# nRF52832_MCU.net
KiCad netlist of a schematic drawn in Altium Designer
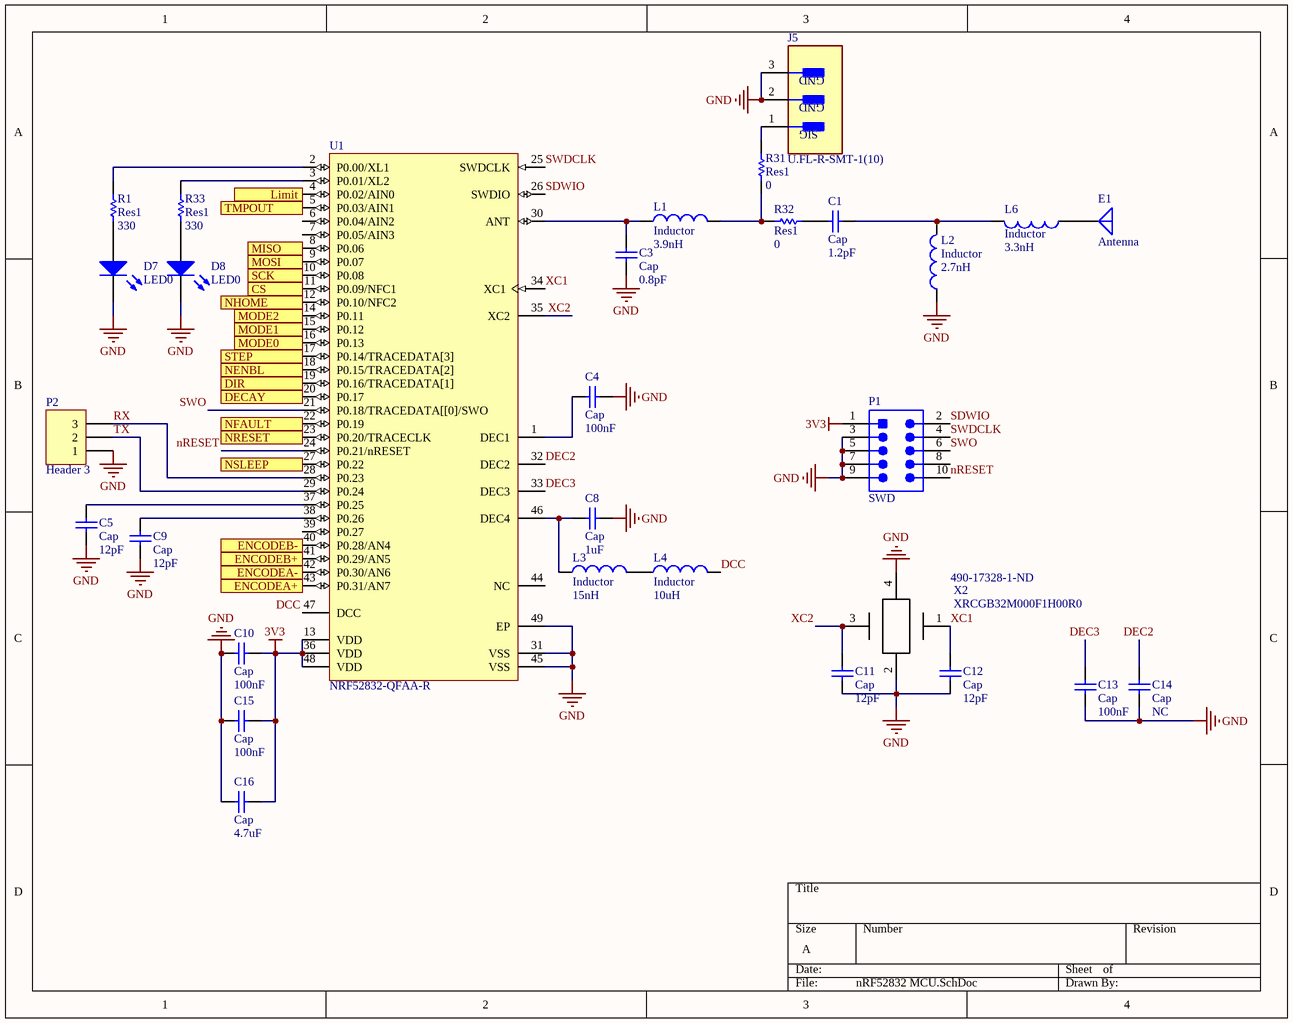
[diagram p0: nRF52832 MCU.SchDoc]

(export (version "E")
  (design (tool "Eeschema 10.0.6"))
  (components
    (comp (ref "C1")
      (value "Cap")
      (footprint "0402-A")
      (description "Capacitor")
      (fields (field (name "ALTIUM_VALUE") "1.2pF") (field (name "PUBLISHER") "Altium Limited"))
      (libsource (lib "Miscellaneous Devices") (part "Cap"))
    )
    (comp (ref "C3")
      (value "Cap")
      (footprint "0402-A")
      (description "Capacitor")
      (fields (field (name "ALTIUM_VALUE") "0.8pF") (field (name "PUBLISHER") "Altium Limited"))
      (libsource (lib "Miscellaneous Devices") (part "Cap"))
    )
    (comp (ref "C4")
      (value "Cap")
      (footprint "1608[0603]")
      (description "Capacitor")
      (fields (field (name "ALTIUM_VALUE") "100nF") (field (name "PUBLISHER") "Altium Limited"))
      (libsource (lib "Miscellaneous Devices") (part "Cap"))
    )
    (comp (ref "C5")
      (value "Cap")
      (footprint "0402-A")
      (description "Capacitor")
      (fields (field (name "ALTIUM_VALUE") "12pF") (field (name "PUBLISHER") "Altium Limited"))
      (libsource (lib "Miscellaneous Devices") (part "Cap"))
    )
    (comp (ref "C8")
      (value "Cap")
      (footprint "1608[0603]")
      (description "Capacitor")
      (fields (field (name "ALTIUM_VALUE") "1uF") (field (name "PUBLISHER") "Altium Limited"))
      (libsource (lib "Miscellaneous Devices") (part "Cap"))
    )
    (comp (ref "C9")
      (value "Cap")
      (footprint "0402-A")
      (description "Capacitor")
      (fields (field (name "ALTIUM_VALUE") "12pF") (field (name "PUBLISHER") "Altium Limited"))
      (libsource (lib "Miscellaneous Devices") (part "Cap"))
    )
    (comp (ref "C10")
      (value "Cap")
      (footprint "1608[0603]")
      (description "Capacitor")
      (fields (field (name "ALTIUM_VALUE") "100nF") (field (name "PUBLISHER") "Altium Limited"))
      (libsource (lib "Miscellaneous Devices") (part "Cap"))
    )
    (comp (ref "C11")
      (value "Cap")
      (footprint "0402-A")
      (description "Capacitor")
      (fields (field (name "ALTIUM_VALUE") "12pF") (field (name "PUBLISHER") "Altium Limited"))
      (libsource (lib "Miscellaneous Devices") (part "Cap"))
    )
    (comp (ref "C12")
      (value "Cap")
      (footprint "0402-A")
      (description "Capacitor")
      (fields (field (name "ALTIUM_VALUE") "12pF") (field (name "PUBLISHER") "Altium Limited"))
      (libsource (lib "Miscellaneous Devices") (part "Cap"))
    )
    (comp (ref "C13")
      (value "Cap")
      (footprint "1608[0603]")
      (description "Capacitor")
      (fields (field (name "ALTIUM_VALUE") "100nF") (field (name "PUBLISHER") "Altium Limited"))
      (libsource (lib "Miscellaneous Devices") (part "Cap"))
    )
    (comp (ref "C14")
      (value "Cap")
      (footprint "0402-A")
      (description "Capacitor")
      (fields (field (name "ALTIUM_VALUE") "NC") (field (name "PUBLISHER") "Altium Limited"))
      (libsource (lib "Miscellaneous Devices") (part "Cap"))
    )
    (comp (ref "C15")
      (value "Cap")
      (footprint "1608[0603]")
      (description "Capacitor")
      (fields (field (name "ALTIUM_VALUE") "100nF") (field (name "PUBLISHER") "Altium Limited"))
      (libsource (lib "Miscellaneous Devices") (part "Cap"))
    )
    (comp (ref "C16")
      (value "Cap")
      (footprint "6-0805_M")
      (description "Capacitor")
      (fields (field (name "ALTIUM_VALUE") "4.7uF") (field (name "PUBLISHER") "Altium Limited"))
      (libsource (lib "Miscellaneous Devices") (part "Cap"))
    )
    (comp (ref "D7")
      (value "LED0")
      (footprint "1608[0603]")
      (fields (field (name "PUBLISHER") "Altium Limited"))
      (libsource (lib "Miscellaneous Devices") (part "LED0"))
    )
    (comp (ref "D8")
      (value "LED0")
      (footprint "1608[0603]")
      (fields (field (name "PUBLISHER") "Altium Limited"))
      (libsource (lib "Miscellaneous Devices") (part "LED0"))
    )
    (comp (ref "E1")
      (value "Antenna")
      (footprint "3.2X1.6X1.1")
      (description "Generic Antenna")
      (fields (field (name "PUBLISHER") "Altium Limited"))
      (libsource (lib "Miscellaneous Devices") (part "Antenna"))
    )
    (comp (ref "J5")
      (value "U.FL-R-SMT-1(10)")
      (footprint "FP-U_FL-R-SMT-1_10-MFG")
      (description "CONN U.FL RCPT STR 50 OHM SMD")
      (libsource (lib "Altium Content Vault") (part "eef6fde44c591823e8076210edfe12f"))
    )
    (comp (ref "L1")
      (value "Inductor")
      (footprint "0402-A")
      (fields (field (name "ALTIUM_VALUE") "3.9nH") (field (name "PUBLISHER") "Altium Limited"))
      (libsource (lib "Miscellaneous Devices") (part "Inductor"))
    )
    (comp (ref "L2")
      (value "Inductor")
      (footprint "0402-A")
      (fields (field (name "ALTIUM_VALUE") "2.7nH") (field (name "PUBLISHER") "Altium Limited"))
      (libsource (lib "Miscellaneous Devices") (part "Inductor"))
    )
    (comp (ref "L3")
      (value "Inductor")
      (footprint "0402-A")
      (fields (field (name "ALTIUM_VALUE") "15nH") (field (name "PUBLISHER") "Altium Limited"))
      (libsource (lib "Miscellaneous Devices") (part "Inductor"))
    )
    (comp (ref "L4")
      (value "Inductor")
      (footprint "1608[0603]")
      (fields (field (name "ALTIUM_VALUE") "10uH") (field (name "PUBLISHER") "Altium Limited"))
      (libsource (lib "Miscellaneous Devices") (part "Inductor"))
    )
    (comp (ref "L6")
      (value "Inductor")
      (footprint "0402-A")
      (fields (field (name "ALTIUM_VALUE") "3.3nH") (field (name "PUBLISHER") "Altium Limited"))
      (libsource (lib "Miscellaneous Devices") (part "Inductor"))
    )
    (comp (ref "P1")
      (value "SWD")
      (footprint "SMTC-FTSH-105-01-L-DV-K_V")
      (description "Male Header, Pitch 1.27 mm, 2 x 5 Position, Height 6.25 mm")
      (fields (field (name "MANUFACTURER") "Samtec"))
      (libsource (lib "Altium Content Vault") (part "CN-2P-M-R10"))
    )
    (comp (ref "P2")
      (value "Header 3")
      (footprint "HDR1X3")
      (description "Header, 3-Pin")
      (fields (field (name "PUBLISHER") "Altium Limited"))
      (libsource (lib "Miscellaneous Connectors") (part "Header 3"))
    )
    (comp (ref "R1")
      (value "Res1")
      (footprint "0402-A")
      (description "Resistor")
      (fields (field (name "ALTIUM_VALUE") "330") (field (name "PUBLISHER") "Altium Limited"))
      (libsource (lib "Miscellaneous Devices") (part "Res1"))
    )
    (comp (ref "R31")
      (value "Res1")
      (footprint "0402-A")
      (description "Resistor")
      (fields (field (name "ALTIUM_VALUE") "0") (field (name "PUBLISHER") "Altium Limited"))
      (libsource (lib "Miscellaneous Devices") (part "Res1"))
    )
    (comp (ref "R32")
      (value "Res1")
      (footprint "0402-A")
      (description "Resistor")
      (fields (field (name "ALTIUM_VALUE") "0") (field (name "PUBLISHER") "Altium Limited"))
      (libsource (lib "Miscellaneous Devices") (part "Res1"))
    )
    (comp (ref "R33")
      (value "Res1")
      (footprint "0402-A")
      (description "Resistor")
      (fields (field (name "ALTIUM_VALUE") "330") (field (name "PUBLISHER") "Altium Limited"))
      (libsource (lib "Miscellaneous Devices") (part "Res1"))
    )
    (comp (ref "U1")
      (value "NRF52832-QFAA-R")
      (footprint "NRSC-QF-48_M")
      (fields (field (name "MANUFACTURER") "Nordic Semiconductor"))
      (libsource (lib "Altium Content Vault") (part "NRSC-NRF52832-QF-48"))
    )
    (comp (ref "X2")
      (value "XRCGB32M000F1H00R0")
      (footprint "XRCGB32M000F1H00R0")
      (description "32MHz Crystal Oscillator")
      (fields (field (name "SUPPLIER PART NUMBER 1") "490-17328-1-ND"))
      (libsource (lib "XRCGB32M000F1H00R0") (part "XRCGB32M000F1H00R0"))
    )
  )
  (nets
    (net (code "1") (name "/CS") (class "Default")
      (node (ref "U1") (pin "11") (pinfunction "P0.09/NFC1_11") (pintype "bidirectional"))
    )
    (net (code "2") (name "/DCC") (class "Default")
      (node (ref "L4") (pin "2") (pinfunction "2_2") (pintype "passive"))
      (node (ref "U1") (pin "47") (pinfunction "DCC_47") (pintype "power_in"))
    )
    (net (code "3") (name "/DEC2") (class "Default")
      (node (ref "C14") (pin "1") (pinfunction "1_1") (pintype "passive"))
      (node (ref "U1") (pin "32") (pinfunction "DEC2_32") (pintype "passive"))
    )
    (net (code "4") (name "/DEC3") (class "Default")
      (node (ref "C13") (pin "1") (pinfunction "1_1") (pintype "passive"))
      (node (ref "U1") (pin "33") (pinfunction "DEC3_33") (pintype "passive"))
    )
    (net (code "5") (name "/DECAY") (class "Default")
      (node (ref "U1") (pin "20") (pinfunction "P0.17_20") (pintype "bidirectional"))
    )
    (net (code "6") (name "/DIR") (class "Default")
      (node (ref "U1") (pin "19") (pinfunction "P0.16/TRACEDATA[1]_19") (pintype "bidirectional"))
    )
    (net (code "7") (name "/ENCODEA+") (class "Default")
      (node (ref "U1") (pin "43") (pinfunction "P0.31/AN7_43") (pintype "bidirectional"))
    )
    (net (code "8") (name "/ENCODEA-") (class "Default")
      (node (ref "U1") (pin "42") (pinfunction "P0.30/AN6_42") (pintype "bidirectional"))
    )
    (net (code "9") (name "/ENCODEB+") (class "Default")
      (node (ref "U1") (pin "41") (pinfunction "P0.29/AN5_41") (pintype "bidirectional"))
    )
    (net (code "10") (name "/ENCODEB-") (class "Default")
      (node (ref "U1") (pin "40") (pinfunction "P0.28/AN4_40") (pintype "bidirectional"))
    )
    (net (code "11") (name "/Limit") (class "Default")
      (node (ref "U1") (pin "4") (pinfunction "P0.02/AIN0_4") (pintype "bidirectional"))
    )
    (net (code "12") (name "/MISO") (class "Default")
      (node (ref "U1") (pin "8") (pinfunction "P0.06_8") (pintype "bidirectional"))
    )
    (net (code "13") (name "/MODE0") (class "Default")
      (node (ref "U1") (pin "16") (pinfunction "P0.13_16") (pintype "bidirectional"))
    )
    (net (code "14") (name "/MODE1") (class "Default")
      (node (ref "U1") (pin "15") (pinfunction "P0.12_15") (pintype "bidirectional"))
    )
    (net (code "15") (name "/MODE2") (class "Default")
      (node (ref "U1") (pin "14") (pinfunction "P0.11_14") (pintype "bidirectional"))
    )
    (net (code "16") (name "/MOSI") (class "Default")
      (node (ref "U1") (pin "9") (pinfunction "P0.07_9") (pintype "bidirectional"))
    )
    (net (code "17") (name "/NENBL") (class "Default")
      (node (ref "U1") (pin "18") (pinfunction "P0.15/TRACEDATA[2]_18") (pintype "bidirectional"))
    )
    (net (code "18") (name "/NFAULT") (class "Default")
      (node (ref "U1") (pin "22") (pinfunction "P0.19_22") (pintype "bidirectional"))
    )
    (net (code "19") (name "/NHOME") (class "Default")
      (node (ref "U1") (pin "12") (pinfunction "P0.10/NFC2_12") (pintype "bidirectional"))
    )
    (net (code "20") (name "/NRESET") (class "Default")
      (node (ref "U1") (pin "23") (pinfunction "P0.20/TRACECLK_23") (pintype "bidirectional"))
    )
    (net (code "21") (name "/NSLEEP") (class "Default")
      (node (ref "U1") (pin "27") (pinfunction "P0.22_27") (pintype "bidirectional"))
    )
    (net (code "22") (name "/RX") (class "Default")
      (node (ref "P2") (pin "3") (pinfunction "3_3") (pintype "passive"))
      (node (ref "U1") (pin "28") (pinfunction "P0.23_28") (pintype "bidirectional"))
    )
    (net (code "23") (name "/SCK") (class "Default")
      (node (ref "U1") (pin "10") (pinfunction "P0.08_10") (pintype "bidirectional"))
    )
    (net (code "24") (name "/SDWIO") (class "Default")
      (node (ref "P1") (pin "2") (pinfunction "2_2") (pintype "passive"))
      (node (ref "U1") (pin "26") (pinfunction "SWDIO_26") (pintype "bidirectional"))
    )
    (net (code "25") (name "/STEP") (class "Default")
      (node (ref "U1") (pin "17") (pinfunction "P0.14/TRACEDATA[3]_17") (pintype "bidirectional"))
    )
    (net (code "26") (name "/SWDCLK") (class "Default")
      (node (ref "P1") (pin "4") (pinfunction "4_4") (pintype "passive"))
      (node (ref "U1") (pin "25") (pinfunction "SWDCLK_25") (pintype "input"))
    )
    (net (code "27") (name "/SWO") (class "Default")
      (node (ref "P1") (pin "6") (pinfunction "6_6") (pintype "passive"))
      (node (ref "U1") (pin "21") (pinfunction "P0.18/TRACEDATA[[0]/SWO_21") (pintype "bidirectional"))
    )
    (net (code "28") (name "/TMPOUT") (class "Default")
      (node (ref "U1") (pin "5") (pinfunction "P0.03/AIN1_5") (pintype "bidirectional"))
    )
    (net (code "29") (name "/TX") (class "Default")
      (node (ref "P2") (pin "2") (pinfunction "2_2") (pintype "passive"))
      (node (ref "U1") (pin "29") (pinfunction "P0.24_29") (pintype "bidirectional"))
    )
    (net (code "30") (name "/XC1") (class "Default")
      (node (ref "C12") (pin "2") (pinfunction "2_2") (pintype "passive"))
      (node (ref "U1") (pin "34") (pinfunction "XC1_34") (pintype "input"))
      (node (ref "X2") (pin "1") (pinfunction "1_1") (pintype "passive"))
    )
    (net (code "31") (name "/XC2") (class "Default")
      (node (ref "C11") (pin "2") (pinfunction "2_2") (pintype "passive"))
      (node (ref "U1") (pin "35") (pinfunction "XC2_35") (pintype "passive"))
      (node (ref "X2") (pin "3") (pintype "passive"))
    )
    (net (code "32") (name "/nRESET") (class "Default")
      (node (ref "P1") (pin "10") (pinfunction "10_10") (pintype "passive"))
      (node (ref "U1") (pin "24") (pinfunction "P0.21/nRESET_24") (pintype "bidirectional"))
    )
    (net (code "33") (name "3V3") (class "Default")
      (node (ref "C10") (pin "1") (pinfunction "1_1") (pintype "passive"))
      (node (ref "C15") (pin "1") (pinfunction "1_1") (pintype "passive"))
      (node (ref "C16") (pin "1") (pinfunction "1_1") (pintype "passive"))
      (node (ref "P1") (pin "1") (pinfunction "1_1") (pintype "passive"))
      (node (ref "U1") (pin "13") (pinfunction "VDD_13") (pintype "power_in"))
      (node (ref "U1") (pin "36") (pinfunction "VDD_36") (pintype "power_in"))
      (node (ref "U1") (pin "48") (pinfunction "VDD_48") (pintype "power_in"))
    )
    (net (code "34") (name "GND") (class "Default")
      (node (ref "C10") (pin "2") (pinfunction "2_2") (pintype "passive"))
      (node (ref "C11") (pin "1") (pinfunction "1_1") (pintype "passive"))
      (node (ref "C12") (pin "1") (pinfunction "1_1") (pintype "passive"))
      (node (ref "C13") (pin "2") (pinfunction "2_2") (pintype "passive"))
      (node (ref "C14") (pin "2") (pinfunction "2_2") (pintype "passive"))
      (node (ref "C15") (pin "2") (pinfunction "2_2") (pintype "passive"))
      (node (ref "C16") (pin "2") (pinfunction "2_2") (pintype "passive"))
      (node (ref "C3") (pin "1") (pinfunction "1_1") (pintype "passive"))
      (node (ref "C4") (pin "1") (pinfunction "1_1") (pintype "passive"))
      (node (ref "C5") (pin "2") (pinfunction "2_2") (pintype "passive"))
      (node (ref "C8") (pin "1") (pinfunction "1_1") (pintype "passive"))
      (node (ref "C9") (pin "2") (pinfunction "2_2") (pintype "passive"))
      (node (ref "D7") (pin "2") (pinfunction "K_2") (pintype "passive"))
      (node (ref "D8") (pin "2") (pinfunction "K_2") (pintype "passive"))
      (node (ref "J5") (pin "2") (pinfunction "GND_2") (pintype "power_in"))
      (node (ref "J5") (pin "3") (pinfunction "GND_3") (pintype "power_in"))
      (node (ref "L2") (pin "1") (pinfunction "1_1") (pintype "passive"))
      (node (ref "P1") (pin "3") (pinfunction "3_3") (pintype "passive"))
      (node (ref "P1") (pin "5") (pinfunction "5_5") (pintype "passive"))
      (node (ref "P1") (pin "7") (pinfunction "7_7") (pintype "passive"))
      (node (ref "P1") (pin "9") (pinfunction "9_9") (pintype "passive"))
      (node (ref "P2") (pin "1") (pinfunction "1_1") (pintype "passive"))
      (node (ref "U1") (pin "31") (pinfunction "VSS_31") (pintype "power_in"))
      (node (ref "U1") (pin "45") (pinfunction "VSS_45") (pintype "power_in"))
      (node (ref "U1") (pin "49") (pinfunction "EP_49") (pintype "power_in"))
      (node (ref "X2") (pin "2") (pinfunction "3_2") (pintype "passive"))
      (node (ref "X2") (pin "4") (pinfunction "4_4") (pintype "passive"))
    )
    (net (code "35") (name "Net-(C1-Pad1)") (class "Default")
      (node (ref "C1") (pin "1") (pinfunction "1_1") (pintype "passive"))
      (node (ref "L2") (pin "2") (pinfunction "2_2") (pintype "passive"))
      (node (ref "L6") (pin "2") (pinfunction "2_2") (pintype "passive"))
    )
    (net (code "36") (name "Net-(C1-Pad2)") (class "Default")
      (node (ref "C1") (pin "2") (pinfunction "2_2") (pintype "passive"))
      (node (ref "R32") (pin "2") (pinfunction "2_2") (pintype "passive"))
    )
    (net (code "37") (name "Net-(D7-A)") (class "Default")
      (node (ref "D7") (pin "1") (pinfunction "A_1") (pintype "passive"))
      (node (ref "R1") (pin "1") (pinfunction "1_1") (pintype "passive"))
    )
    (net (code "38") (name "Net-(D8-A)") (class "Default")
      (node (ref "D8") (pin "1") (pinfunction "A_1") (pintype "passive"))
      (node (ref "R33") (pin "1") (pinfunction "1_1") (pintype "passive"))
    )
    (net (code "39") (name "Net-(E1-A)") (class "Default")
      (node (ref "E1") (pin "1") (pinfunction "A_1") (pintype "passive"))
      (node (ref "L6") (pin "1") (pinfunction "1_1") (pintype "passive"))
    )
    (net (code "40") (name "Net-(J5-SIG)") (class "Default")
      (node (ref "J5") (pin "1") (pinfunction "SIG_1") (pintype "passive"))
      (node (ref "R31") (pin "2") (pinfunction "2_2") (pintype "passive"))
    )
    (net (code "41") (name "Net-(L1-Pad2)") (class "Default")
      (node (ref "L1") (pin "2") (pinfunction "2_2") (pintype "passive"))
      (node (ref "R31") (pin "1") (pinfunction "1_1") (pintype "passive"))
      (node (ref "R32") (pin "1") (pinfunction "1_1") (pintype "passive"))
    )
    (net (code "42") (name "Net-(L3-Pad2)") (class "Default")
      (node (ref "L3") (pin "2") (pinfunction "2_2") (pintype "passive"))
      (node (ref "L4") (pin "1") (pinfunction "1_1") (pintype "passive"))
    )
    (net (code "43") (name "Net-(U1-ANT)") (class "Default")
      (node (ref "C3") (pin "2") (pinfunction "2_2") (pintype "passive"))
      (node (ref "L1") (pin "1") (pinfunction "1_1") (pintype "passive"))
      (node (ref "U1") (pin "30") (pinfunction "ANT_30") (pintype "bidirectional"))
    )
    (net (code "44") (name "Net-(U1-DEC1)") (class "Default")
      (node (ref "C4") (pin "2") (pinfunction "2_2") (pintype "passive"))
      (node (ref "U1") (pin "1") (pinfunction "DEC1_1") (pintype "passive"))
    )
    (net (code "45") (name "Net-(U1-DEC4)") (class "Default")
      (node (ref "C8") (pin "2") (pinfunction "2_2") (pintype "passive"))
      (node (ref "L3") (pin "1") (pinfunction "1_1") (pintype "passive"))
      (node (ref "U1") (pin "46") (pinfunction "DEC4_46") (pintype "passive"))
    )
    (net (code "46") (name "Net-(U1-P0.00{slash}XL1)") (class "Default")
      (node (ref "R1") (pin "2") (pinfunction "2_2") (pintype "passive"))
      (node (ref "U1") (pin "2") (pinfunction "P0.00/XL1_2") (pintype "bidirectional"))
    )
    (net (code "47") (name "Net-(U1-P0.01{slash}XL2)") (class "Default")
      (node (ref "R33") (pin "2") (pinfunction "2_2") (pintype "passive"))
      (node (ref "U1") (pin "3") (pinfunction "P0.01/XL2_3") (pintype "bidirectional"))
    )
    (net (code "48") (name "Net-(U1-P0.25)") (class "Default")
      (node (ref "C5") (pin "1") (pinfunction "1_1") (pintype "passive"))
      (node (ref "U1") (pin "37") (pinfunction "P0.25_37") (pintype "bidirectional"))
    )
    (net (code "49") (name "Net-(U1-P0.26)") (class "Default")
      (node (ref "C9") (pin "1") (pinfunction "1_1") (pintype "passive"))
      (node (ref "U1") (pin "38") (pinfunction "P0.26_38") (pintype "bidirectional"))
    )
    (net (code "50") (name "unconnected-(P1-Pad8)") (class "Default")
      (node (ref "P1") (pin "8") (pinfunction "8_8") (pintype "passive"))
    )
    (net (code "51") (name "unconnected-(U1-NC-Pad44)") (class "Default")
      (node (ref "U1") (pin "44") (pinfunction "NC_44") (pintype "passive"))
    )
    (net (code "52") (name "unconnected-(U1-P0.04{slash}AIN2-Pad6)") (class "Default")
      (node (ref "U1") (pin "6") (pinfunction "P0.04/AIN2_6") (pintype "bidirectional"))
    )
    (net (code "53") (name "unconnected-(U1-P0.05{slash}AIN3-Pad7)") (class "Default")
      (node (ref "U1") (pin "7") (pinfunction "P0.05/AIN3_7") (pintype "bidirectional"))
    )
    (net (code "54") (name "unconnected-(U1-P0.27-Pad39)") (class "Default")
      (node (ref "U1") (pin "39") (pinfunction "P0.27_39") (pintype "bidirectional"))
    )
  )
)
